# Tomo_SMT.net
KiCad netlist of a schematic drawn in EAGLE
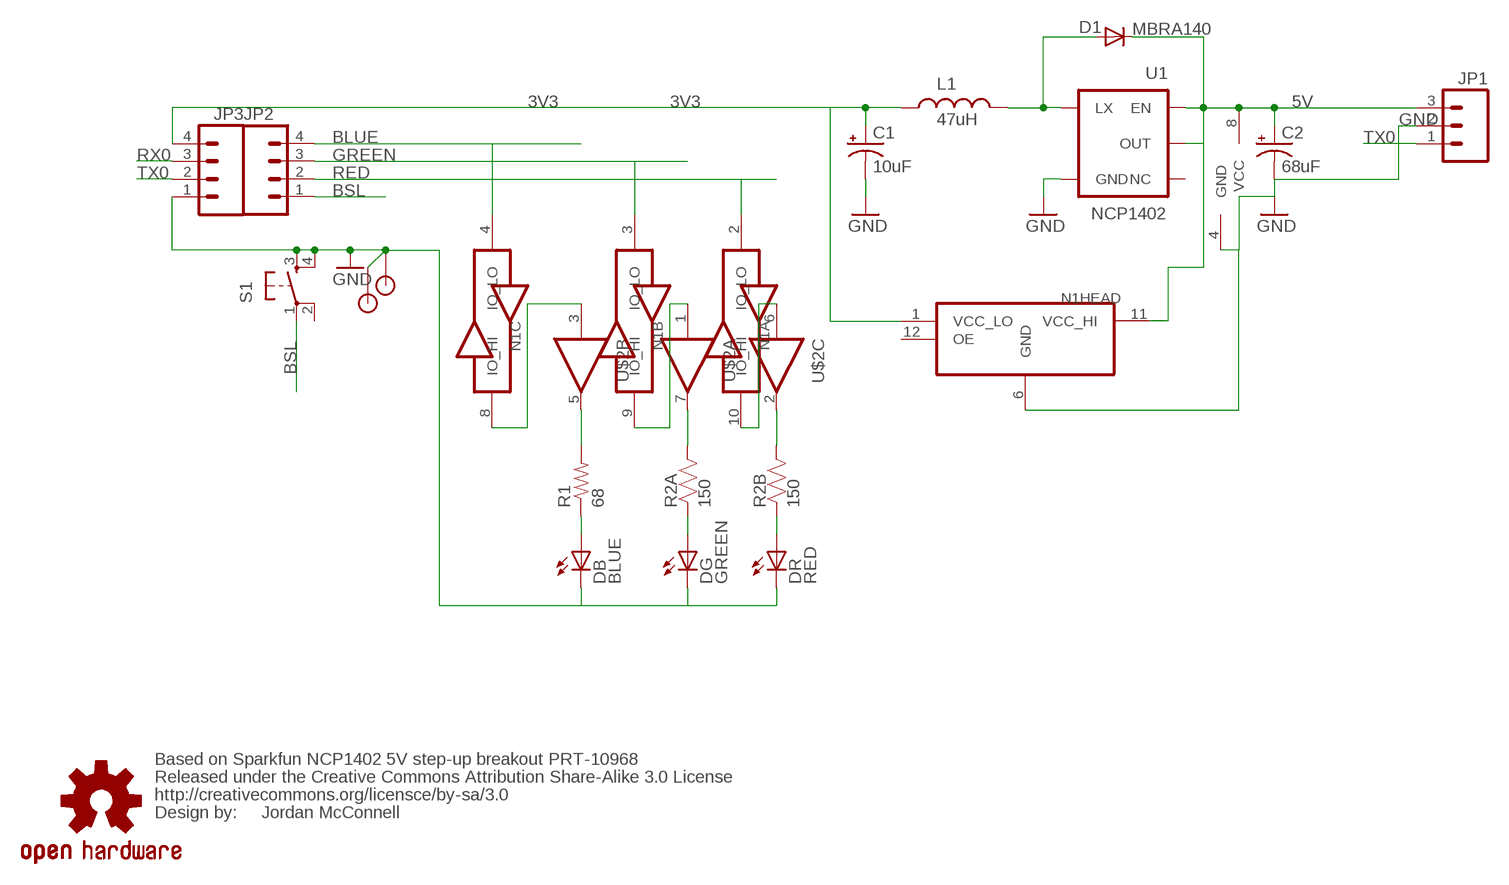
[diagram p0: schematic, sheet 1]

(export (version "E")
  (design (tool "Eeschema 10.0.6"))
  (components
    (comp (ref "C1")
      (value "10uF")
      (footprint "eagle-import:EIA3216")
      (libsource (lib "eagle-import") (part "CAP_POL1206"))
    )
    (comp (ref "C2")
      (value "68uF")
      (footprint "eagle-import:EIA3528")
      (libsource (lib "eagle-import") (part "CAP_POL3528"))
    )
    (comp (ref "D1")
      (value "MBRA140")
      (footprint "eagle-import:SMA-DIODE")
      (libsource (lib "eagle-import") (part "DIODESMA"))
    )
    (comp (ref "DB")
      (value "BLUE")
      (footprint "eagle-import:LED5MM")
      (libsource (lib "eagle-import") (part "LED5MM"))
    )
    (comp (ref "DG")
      (value "GREEN")
      (footprint "eagle-import:LED5MM")
      (libsource (lib "eagle-import") (part "LED5MM"))
    )
    (comp (ref "DR")
      (value "RED")
      (footprint "eagle-import:LED5MM")
      (libsource (lib "eagle-import") (part "LED5MM"))
    )
    (comp (ref "JP1")
      (value "M03PTH")
      (footprint "eagle-import:1X03")
      (libsource (lib "eagle-import") (part "M03PTH"))
    )
    (comp (ref "JP2")
      (value "M04PTH")
      (footprint "eagle-import:1X04")
      (libsource (lib "eagle-import") (part "M04PTH"))
    )
    (comp (ref "JP3")
      (value "M04PTH")
      (footprint "eagle-import:1X04")
      (libsource (lib "eagle-import") (part "M04PTH"))
    )
    (comp (ref "L1")
      (value "47uH")
      (footprint "eagle-import:RADIAL_5MM")
      (libsource (lib "eagle-import") (part "INDUCTORRCH-895"))
    )
    (comp (ref "N1")
      (value "TXB0104RUT")
      (footprint "eagle-import:R-PUQFN-N12")
      (libsource (lib "eagle-import") (part "TXB0104RUT"))
    )
    (comp (ref "R1")
      (value "68")
      (footprint "eagle-import:0402-RES")
      (libsource (lib "eagle-import") (part "RESISTOR0402-RES"))
    )
    (comp (ref "R2")
      (value "150")
      (footprint "eagle-import:CRA02")
      (libsource (lib "eagle-import") (part "RP2EXB24V"))
    )
    (comp (ref "S1")
      (value "TAC_SWITCHPTH")
      (footprint "eagle-import:TACTILE-PTH")
      (libsource (lib "eagle-import") (part "TAC_SWITCHPTH"))
    )
    (comp (ref "U$1")
      (value "OSHW-LOGOL")
      (footprint "eagle-import:OSHW-LOGO-L")
      (libsource (lib "eagle-import") (part "OSHW-LOGOL"))
    )
    (comp (ref "U$2")
      (value "743G34")
      (footprint "eagle-import:DCT")
      (libsource (lib "eagle-import") (part "743G34"))
    )
    (comp (ref "U$3")
      (value "STANDOFF")
      (footprint "eagle-import:STANDOFF")
      (libsource (lib "eagle-import") (part "STANDOFF"))
    )
    (comp (ref "U$4")
      (value "STANDOFF")
      (footprint "eagle-import:STANDOFF")
      (libsource (lib "eagle-import") (part "STANDOFF"))
    )
    (comp (ref "U1")
      (value "NCP1402")
      (footprint "eagle-import:SOT23-5")
      (libsource (lib "eagle-import") (part "V_REG_NCP1400SOT23-5"))
    )
  )
  (nets
    (net (code "1") (name "/3V3") (class "Default")
      (node (ref "C1") (pin "A") (pinfunction "+_A") (pintype "passive"))
      (node (ref "JP3") (pin "4") (pinfunction "4_4") (pintype "passive"))
      (node (ref "L1") (pin "1") (pinfunction "1_1") (pintype "passive"))
      (node (ref "N1") (pin "1") (pinfunction "VCC_LO_1") (pintype "power_in"))
    )
    (net (code "2") (name "/5V") (class "Default")
      (node (ref "C2") (pin "A") (pinfunction "+_A") (pintype "passive"))
      (node (ref "D1") (pin "C") (pinfunction "C_C") (pintype "passive"))
      (node (ref "JP1") (pin "3") (pinfunction "3_3") (pintype "passive"))
      (node (ref "N1") (pin "11") (pinfunction "VCC_HI_11") (pintype "power_in"))
      (node (ref "U$2") (pin "8") (pinfunction "VCC_8") (pintype "bidirectional"))
      (node (ref "U1") (pin "1") (pinfunction "EN_1") (pintype "input"))
      (node (ref "U1") (pin "2") (pinfunction "OUT_2") (pintype "passive"))
    )
    (net (code "3") (name "/BLUE") (class "Default")
      (node (ref "JP2") (pin "4") (pinfunction "4_4") (pintype "passive"))
      (node (ref "N1") (pin "4") (pinfunction "IO_LO_4") (pintype "bidirectional"))
    )
    (net (code "4") (name "/BSL") (class "Default")
      (node (ref "JP2") (pin "1") (pinfunction "1_1") (pintype "passive"))
      (node (ref "S1") (pin "1") (pinfunction "1_1") (pintype "passive"))
    )
    (net (code "5") (name "/GREEN") (class "Default")
      (node (ref "JP2") (pin "3") (pinfunction "3_3") (pintype "passive"))
      (node (ref "N1") (pin "3") (pinfunction "IO_LO_3") (pintype "bidirectional"))
    )
    (net (code "6") (name "/RED") (class "Default")
      (node (ref "JP2") (pin "2") (pinfunction "2_2") (pintype "passive"))
      (node (ref "N1") (pin "2") (pinfunction "IO_LO_2") (pintype "bidirectional"))
    )
    (net (code "7") (name "/RX0") (class "Default")
      (node (ref "JP3") (pin "3") (pinfunction "3_3") (pintype "passive"))
    )
    (net (code "8") (name "/TX0") (class "Default")
      (node (ref "JP1") (pin "1") (pinfunction "1_1") (pintype "passive"))
      (node (ref "JP3") (pin "2") (pinfunction "2_2") (pintype "passive"))
    )
    (net (code "9") (name "GND") (class "Default")
      (node (ref "C1") (pin "C") (pinfunction "-_C") (pintype "passive"))
      (node (ref "C2") (pin "C") (pinfunction "-_C") (pintype "passive"))
      (node (ref "DB") (pin "K") (pinfunction "C_K") (pintype "passive"))
      (node (ref "DG") (pin "K") (pinfunction "C_K") (pintype "passive"))
      (node (ref "DR") (pin "K") (pinfunction "C_K") (pintype "passive"))
      (node (ref "JP1") (pin "2") (pinfunction "2_2") (pintype "passive"))
      (node (ref "JP3") (pin "1") (pinfunction "1_1") (pintype "passive"))
      (node (ref "N1") (pin "6") (pinfunction "GND_6") (pintype "power_in"))
      (node (ref "S1") (pin "3") (pinfunction "3_3") (pintype "passive"))
      (node (ref "S1") (pin "4") (pinfunction "4_4") (pintype "passive"))
      (node (ref "U$2") (pin "4") (pinfunction "GND_4") (pintype "bidirectional"))
      (node (ref "U$3") (pin "P$1") (pinfunction "P$1_P$1") (pintype "bidirectional"))
      (node (ref "U$4") (pin "P$1") (pinfunction "P$1_P$1") (pintype "bidirectional"))
      (node (ref "U1") (pin "4") (pinfunction "GND_4") (pintype "input"))
    )
    (net (code "10") (name "Net-(DB-PadA)") (class "Default")
      (node (ref "DB") (pin "A") (pinfunction "A_A") (pintype "passive"))
      (node (ref "R1") (pin "1") (pinfunction "1_1") (pintype "passive"))
    )
    (net (code "11") (name "Net-(DG-PadA)") (class "Default")
      (node (ref "DG") (pin "A") (pinfunction "A_A") (pintype "passive"))
      (node (ref "R2") (pin "1") (pinfunction "1_1") (pintype "passive"))
    )
    (net (code "12") (name "Net-(N1A-IO_HI)") (class "Default")
      (node (ref "N1") (pin "10") (pinfunction "IO_HI_10") (pintype "bidirectional"))
      (node (ref "U$2") (pin "6") (pinfunction "IN_6") (pintype "input"))
    )
    (net (code "13") (name "Net-(N1B-IO_HI)") (class "Default")
      (node (ref "N1") (pin "9") (pinfunction "IO_HI_9") (pintype "bidirectional"))
      (node (ref "U$2") (pin "1") (pinfunction "IN_1") (pintype "input"))
    )
    (net (code "14") (name "Net-(N1C-IO_HI)") (class "Default")
      (node (ref "N1") (pin "8") (pinfunction "IO_HI_8") (pintype "bidirectional"))
      (node (ref "U$2") (pin "3") (pinfunction "IN_3") (pintype "input"))
    )
    (net (code "15") (name "Net-(R2A-2)") (class "Default")
      (node (ref "R2") (pin "4") (pinfunction "2_4") (pintype "passive"))
      (node (ref "U$2") (pin "7") (pinfunction "OUT_7") (pintype "bidirectional"))
    )
    (net (code "16") (name "Net-(R2B-1)") (class "Default")
      (node (ref "DR") (pin "A") (pinfunction "A_A") (pintype "passive"))
      (node (ref "R2") (pin "2") (pinfunction "1_2") (pintype "passive"))
    )
    (net (code "17") (name "Net-(R2B-2)") (class "Default")
      (node (ref "R2") (pin "3") (pinfunction "2_3") (pintype "passive"))
      (node (ref "U$2") (pin "2") (pinfunction "OUT_2") (pintype "bidirectional"))
    )
    (net (code "18") (name "Net-(U$2B-OUT)") (class "Default")
      (node (ref "R1") (pin "2") (pinfunction "2_2") (pintype "passive"))
      (node (ref "U$2") (pin "5") (pinfunction "OUT_5") (pintype "bidirectional"))
    )
    (net (code "19") (name "Net-(U1-LX)") (class "Default")
      (node (ref "D1") (pin "A") (pinfunction "A_A") (pintype "passive"))
      (node (ref "L1") (pin "2") (pinfunction "2_2") (pintype "passive"))
      (node (ref "U1") (pin "5") (pinfunction "LX_5") (pintype "input"))
    )
    (net (code "20") (name "unconnected-(N1E-OE-Pad12)") (class "Default")
      (node (ref "N1") (pin "12") (pinfunction "OE_12") (pintype "bidirectional"))
    )
    (net (code "21") (name "unconnected-(S1-Pad2)") (class "Default")
      (node (ref "S1") (pin "2") (pinfunction "2_2") (pintype "passive"))
    )
    (net (code "22") (name "unconnected-(U1-NC-Pad3)") (class "Default")
      (node (ref "U1") (pin "3") (pinfunction "NC_3") (pintype "input"))
    )
  )
)
